# FQP30N06L_H_Bridge.net
KiCad netlist of a schematic drawn in EAGLE
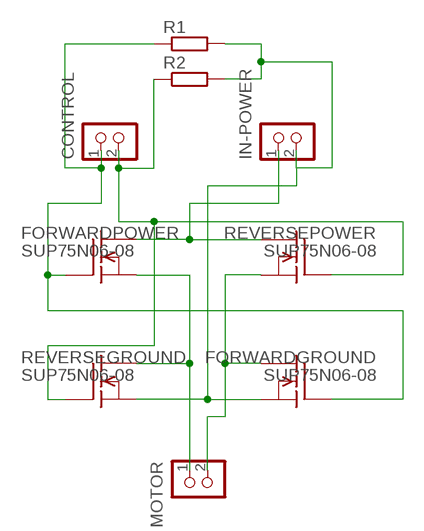
[diagram p0: schematic, sheet 1]

(export (version "E")
  (design (tool "Eeschema 10.0.6"))
  (components
    (comp (ref "CONTROL")
      (value "CON_HEADER_1X02-PTH")
      (footprint "eagle-import:M1X2")
      (libsource (lib "eagle-import") (part "CON_HEADER_1X02-PTH"))
    )
    (comp (ref "FORWARDGROUND")
      (value "SUP75N06-08")
      (footprint "eagle-import:TO220")
      (libsource (lib "eagle-import") (part "SUP75N06-08"))
    )
    (comp (ref "FORWARDPOWER")
      (value "SUP75N06-08")
      (footprint "eagle-import:TO220")
      (libsource (lib "eagle-import") (part "SUP75N06-08"))
    )
    (comp (ref "IN-POWER")
      (value "CON_HEADER_1X02-PTH")
      (footprint "eagle-import:M1X2")
      (libsource (lib "eagle-import") (part "CON_HEADER_1X02-PTH"))
    )
    (comp (ref "MOTOR")
      (value "CON_HEADER_1X02-PTH")
      (footprint "eagle-import:M1X2")
      (libsource (lib "eagle-import") (part "CON_HEADER_1X02-PTH"))
    )
    (comp (ref "R1")
      (value "RESISTOR-PTH-0.4")
      (footprint "eagle-import:RTH025W")
      (libsource (lib "eagle-import") (part "RESISTOR-PTH-0.4"))
    )
    (comp (ref "R2")
      (value "RESISTOR-PTH-0.4")
      (footprint "eagle-import:RTH025W")
      (libsource (lib "eagle-import") (part "RESISTOR-PTH-0.4"))
    )
    (comp (ref "REVERSEGROUND")
      (value "SUP75N06-08")
      (footprint "eagle-import:TO220")
      (libsource (lib "eagle-import") (part "SUP75N06-08"))
    )
    (comp (ref "REVERSEPOWER")
      (value "SUP75N06-08")
      (footprint "eagle-import:TO220")
      (libsource (lib "eagle-import") (part "SUP75N06-08"))
    )
  )
  (nets
    (net (code "1") (name "Net-(FORWARDGROUND-D)") (class "Default")
      (node (ref "FORWARDGROUND") (pin "2") (pinfunction "D_2") (pintype "passive"))
      (node (ref "MOTOR") (pin "2") (pinfunction "2_2") (pintype "passive"))
      (node (ref "REVERSEPOWER") (pin "3") (pinfunction "S_3") (pintype "passive"))
    )
    (net (code "2") (name "Net-(FORWARDGROUND-G)") (class "Default")
      (node (ref "CONTROL") (pin "1") (pinfunction "1_1") (pintype "passive"))
      (node (ref "FORWARDGROUND") (pin "1") (pinfunction "G_1") (pintype "passive"))
      (node (ref "FORWARDPOWER") (pin "1") (pinfunction "G_1") (pintype "passive"))
      (node (ref "R1") (pin "1") (pinfunction "1_1") (pintype "passive"))
    )
    (net (code "3") (name "Net-(FORWARDGROUND-S)") (class "Default")
      (node (ref "FORWARDGROUND") (pin "3") (pinfunction "S_3") (pintype "passive"))
      (node (ref "IN-POWER") (pin "2") (pinfunction "2_2") (pintype "passive"))
      (node (ref "R1") (pin "2") (pinfunction "2_2") (pintype "passive"))
      (node (ref "R2") (pin "2") (pinfunction "2_2") (pintype "passive"))
      (node (ref "REVERSEGROUND") (pin "3") (pinfunction "S_3") (pintype "passive"))
    )
    (net (code "4") (name "Net-(FORWARDPOWER-D)") (class "Default")
      (node (ref "FORWARDPOWER") (pin "2") (pinfunction "D_2") (pintype "passive"))
      (node (ref "IN-POWER") (pin "1") (pinfunction "1_1") (pintype "passive"))
      (node (ref "REVERSEPOWER") (pin "2") (pinfunction "D_2") (pintype "passive"))
    )
    (net (code "5") (name "Net-(FORWARDPOWER-S)") (class "Default")
      (node (ref "FORWARDPOWER") (pin "3") (pinfunction "S_3") (pintype "passive"))
      (node (ref "MOTOR") (pin "1") (pinfunction "1_1") (pintype "passive"))
      (node (ref "REVERSEGROUND") (pin "2") (pinfunction "D_2") (pintype "passive"))
    )
    (net (code "6") (name "Net-(REVERSEGROUND-G)") (class "Default")
      (node (ref "CONTROL") (pin "2") (pinfunction "2_2") (pintype "passive"))
      (node (ref "R2") (pin "1") (pinfunction "1_1") (pintype "passive"))
      (node (ref "REVERSEGROUND") (pin "1") (pinfunction "G_1") (pintype "passive"))
      (node (ref "REVERSEPOWER") (pin "1") (pinfunction "G_1") (pintype "passive"))
    )
  )
)
